# time_circuit_controller_1_2.net
KiCad netlist of a schematic drawn in EAGLE
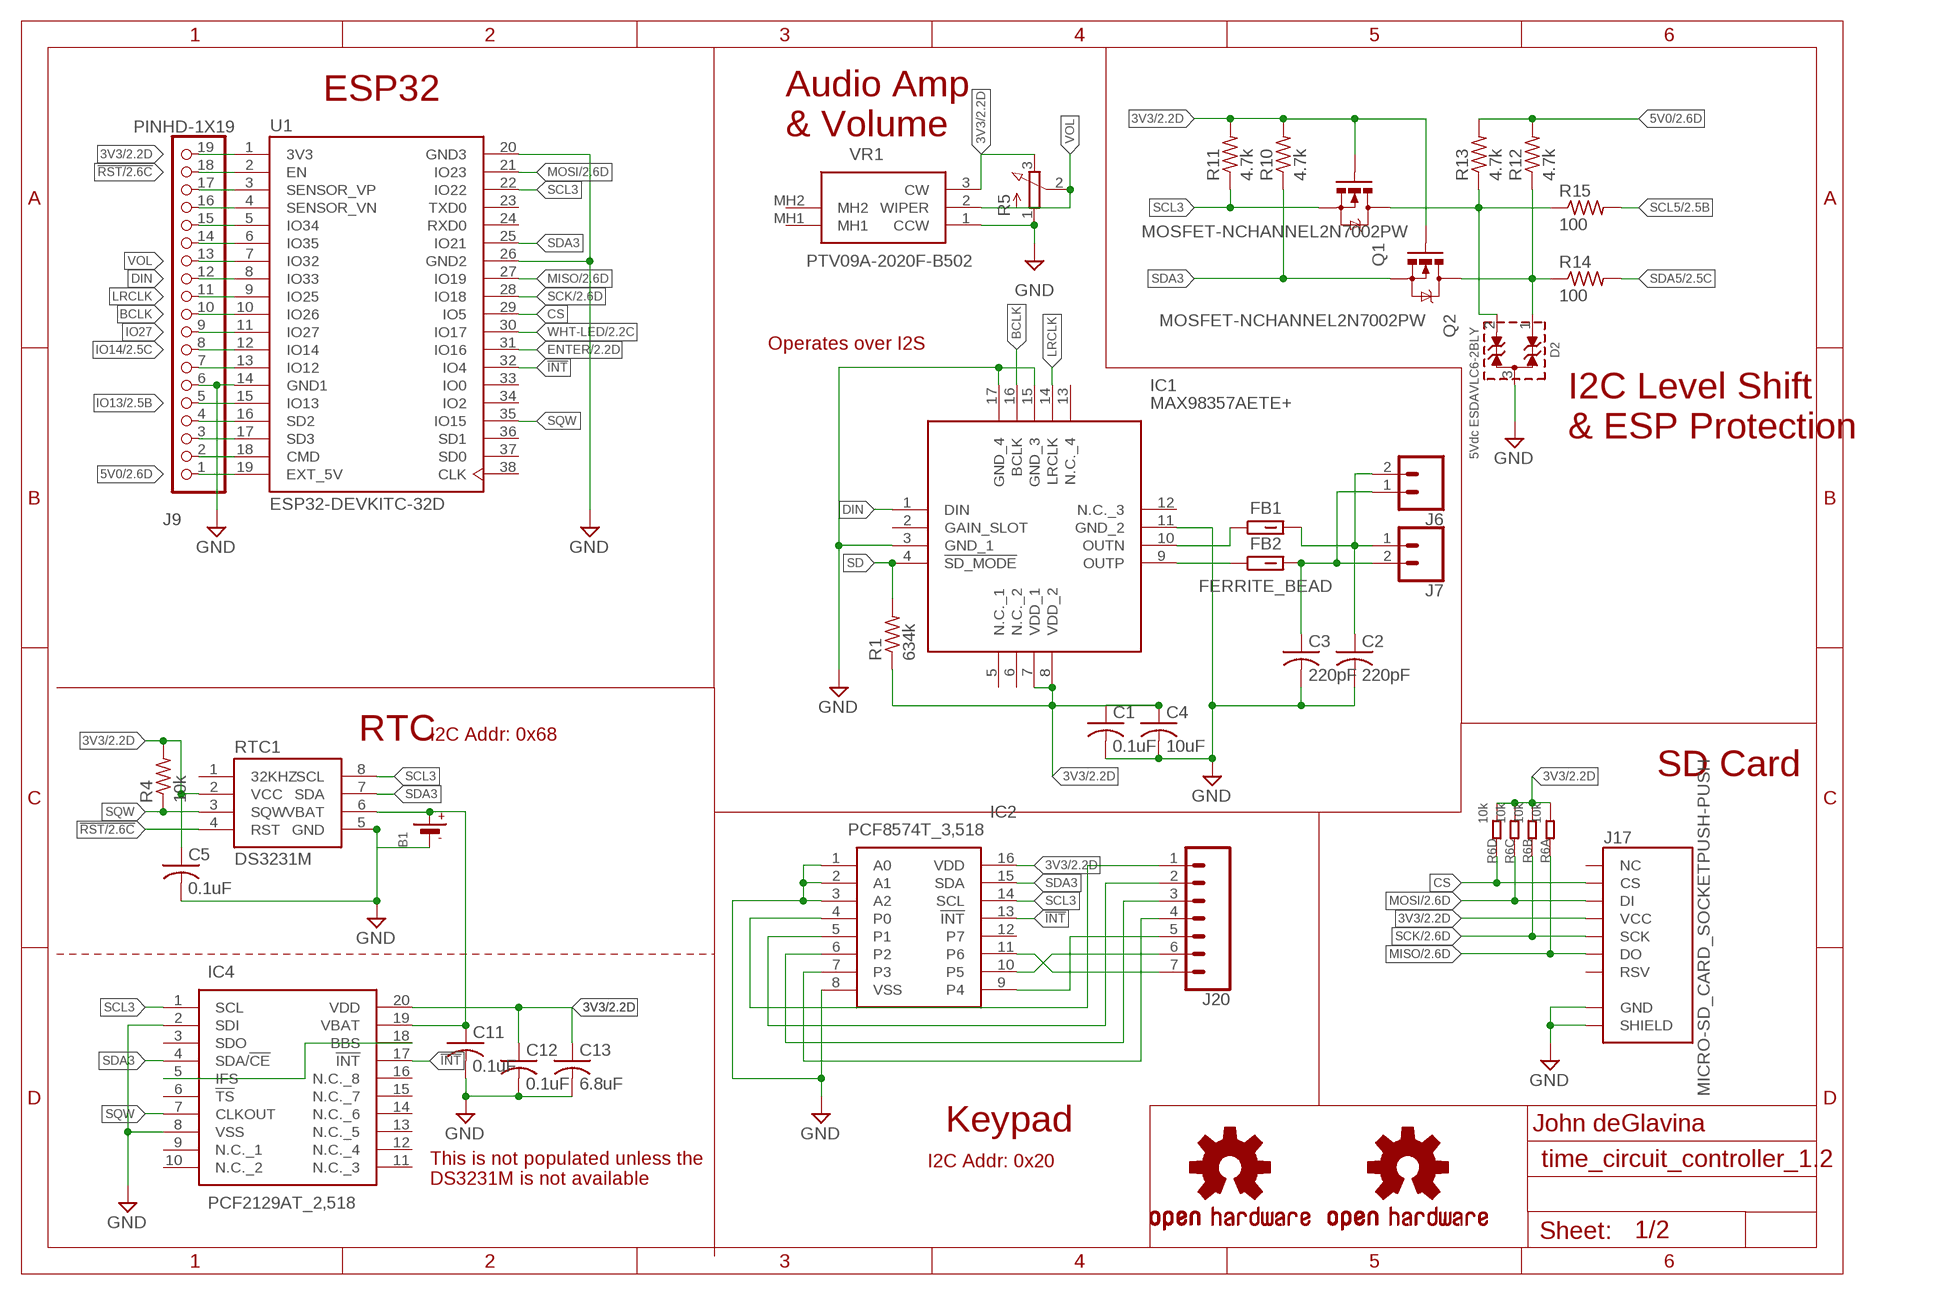
[diagram p0: schematic, sheet 1]
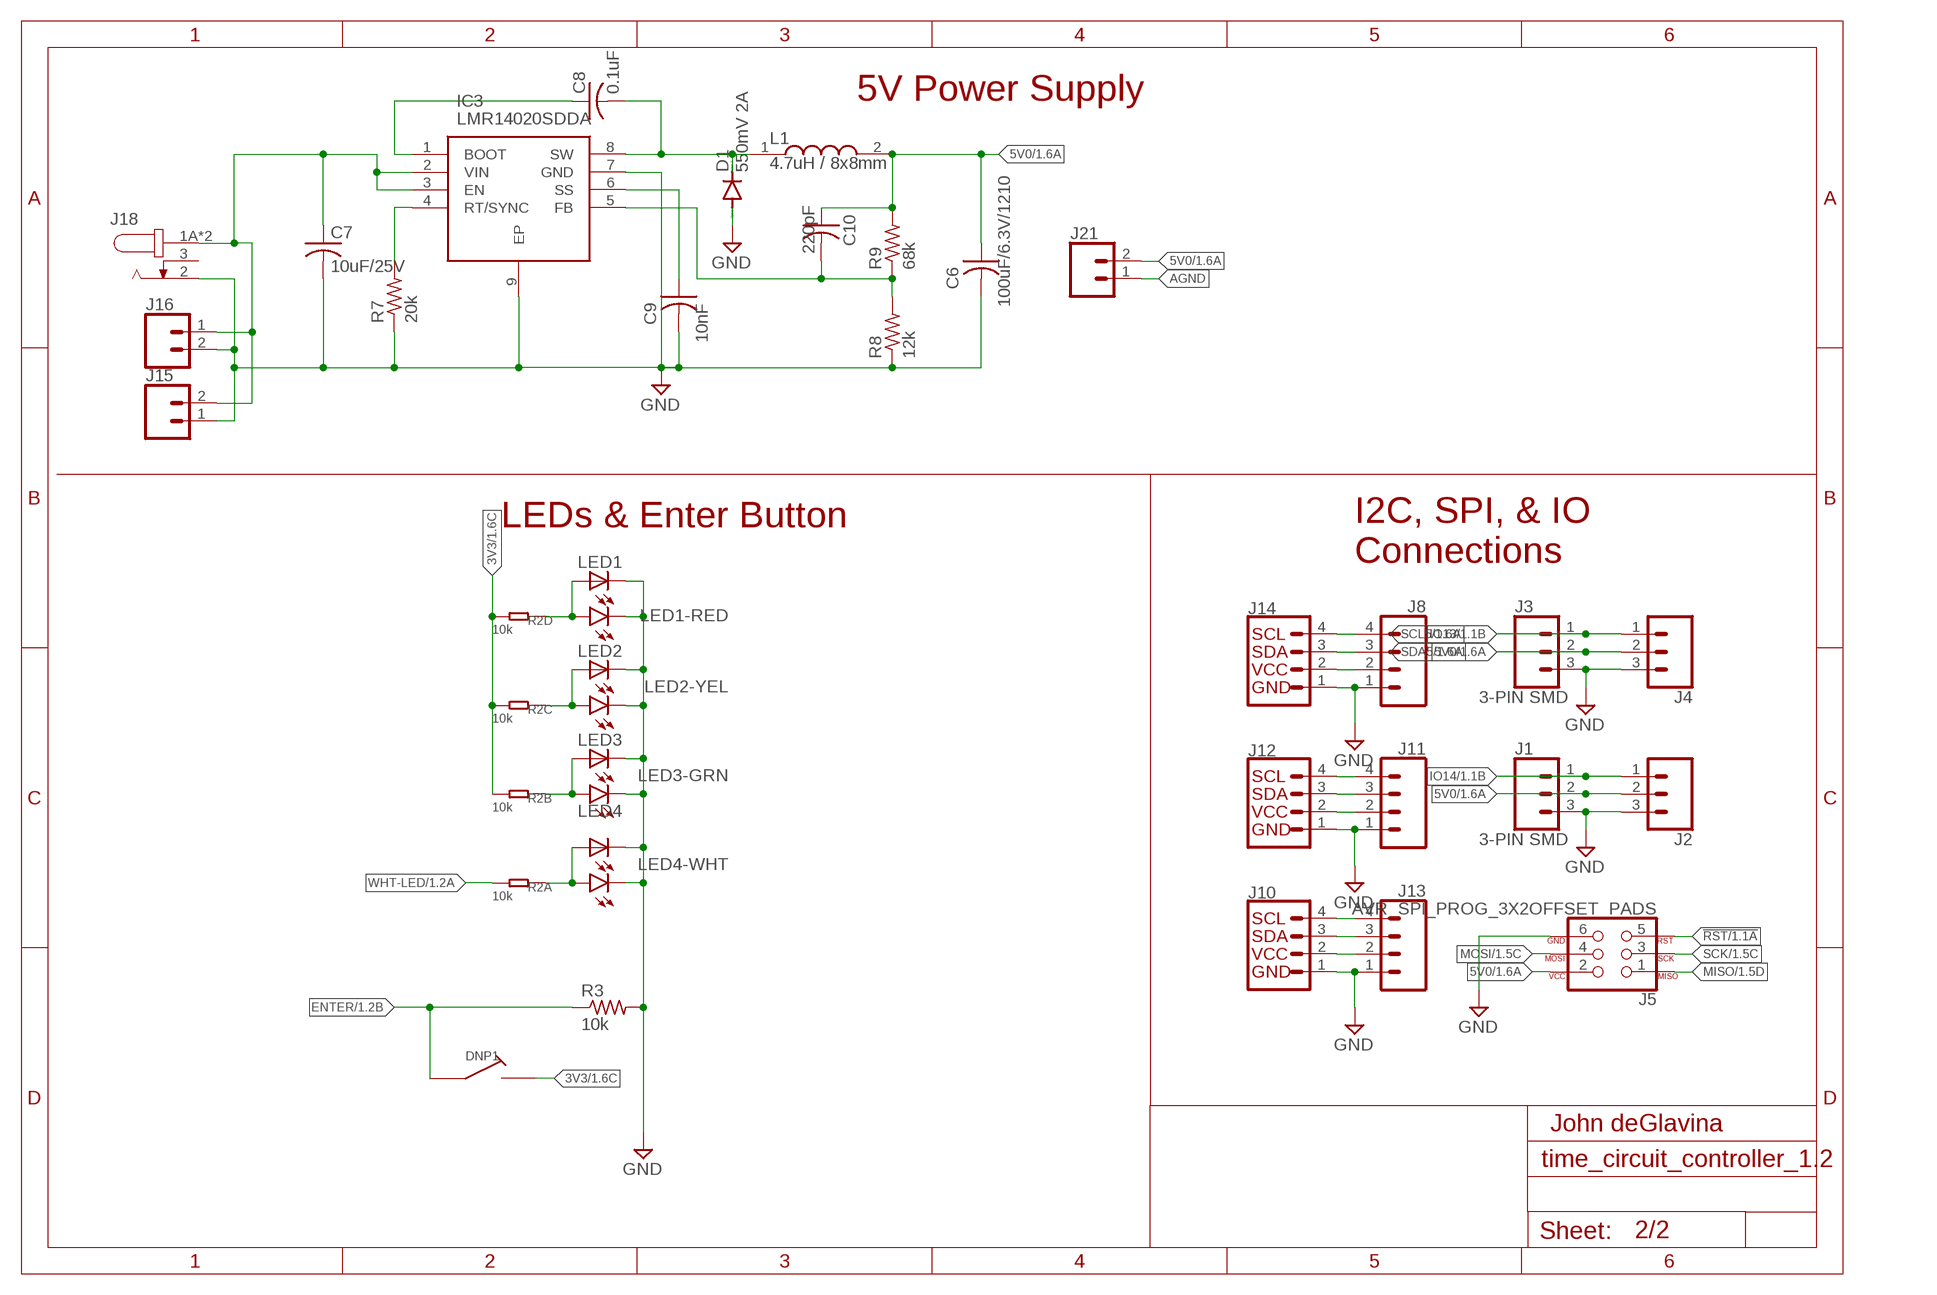
[diagram p1: schematic, sheet 2]

(export (version "E")
  (design (tool "Eeschema 10.0.6"))
  (components
    (comp (ref "C6")
      (value "100uF/6.3V/1210")
      (footprint "eagle-import:C1210")
      (libsource (lib "eagle-import") (part "C-USC1210"))
    )
    (comp (ref "C7")
      (value "10uF/25V")
      (footprint "eagle-import:C0805")
      (libsource (lib "eagle-import") (part "C-USC0805"))
    )
    (comp (ref "C8")
      (value "0.1uF")
      (footprint "eagle-import:C0603")
      (libsource (lib "eagle-import") (part "C-USC0603"))
    )
    (comp (ref "C9")
      (value "10nF")
      (footprint "eagle-import:C0603")
      (libsource (lib "eagle-import") (part "C-USC0603"))
    )
    (comp (ref "C10")
      (value "220pF")
      (footprint "eagle-import:C0603")
      (libsource (lib "eagle-import") (part "C-USC0603"))
    )
    (comp (ref "D1")
      (value "550mV 2A")
      (footprint "eagle-import:DO214AC")
      (libsource (lib "eagle-import") (part "DIODE-DO214AC"))
    )
    (comp (ref "DNP1")
      (value "SWITCH-PINHEAD")
      (footprint "eagle-import:PIN-1X2-3.5MM")
      (libsource (lib "eagle-import") (part "SWITCH-PINHEAD"))
    )
    (comp (ref "IC3")
      (value "LMR14020SDDA")
      (footprint "eagle-import:SOIC127P600X170-9N")
      (fields
        (field (name "MOUSER_PART_NUMBER") "595-LMR14020SDDA")
        (field (name "RS_PART_NUMBER") "1629813")
      )
      (libsource (lib "eagle-import") (part "LMR14020SDDA"))
    )
    (comp (ref "J1")
      (value "3-PIN SMD")
      (footprint "eagle-import:JST-3-SMD")
      (libsource (lib "eagle-import") (part "CONN_03JST-SMD"))
    )
    (comp (ref "J2")
      (value "CONN_03LOCK_LONGPADS")
      (footprint "eagle-import:1X03_LOCK_LONGPADS")
      (libsource (lib "eagle-import") (part "CONN_03LOCK_LONGPADS"))
    )
    (comp (ref "J3")
      (value "3-PIN SMD")
      (footprint "eagle-import:JST-3-SMD")
      (libsource (lib "eagle-import") (part "CONN_03JST-SMD"))
    )
    (comp (ref "J4")
      (value "CONN_03LOCK_LONGPADS")
      (footprint "eagle-import:1X03_LOCK_LONGPADS")
      (libsource (lib "eagle-import") (part "CONN_03LOCK_LONGPADS"))
    )
    (comp (ref "J5")
      (value "AVR_SPI_PROG_3X2OFFSET_PADS")
      (footprint "eagle-import:2X3_OFFSET")
      (libsource (lib "eagle-import") (part "AVR_SPI_PROG_3X2OFFSET_PADS"))
    )
    (comp (ref "J8")
      (value "CONN_04SMD_2.54")
      (footprint "eagle-import:1X04_5.5MM_STRAIGHT")
      (libsource (lib "eagle-import") (part "CONN_04SMD_2.54"))
    )
    (comp (ref "J10")
      (value "I2C_STANDARD")
      (footprint "eagle-import:1X04")
      (libsource (lib "eagle-import") (part "I2C_STANDARD"))
    )
    (comp (ref "J11")
      (value "CONN_04SMD_2.54")
      (footprint "eagle-import:1X04_5.5MM_STRAIGHT")
      (libsource (lib "eagle-import") (part "CONN_04SMD_2.54"))
    )
    (comp (ref "J12")
      (value "I2C_STANDARD")
      (footprint "eagle-import:1X04")
      (libsource (lib "eagle-import") (part "I2C_STANDARD"))
    )
    (comp (ref "J13")
      (value "CONN_04SMD_2.54")
      (footprint "eagle-import:1X04_5.5MM_STRAIGHT")
      (libsource (lib "eagle-import") (part "CONN_04SMD_2.54"))
    )
    (comp (ref "J14")
      (value "I2C_STANDARD")
      (footprint "eagle-import:1X04")
      (libsource (lib "eagle-import") (part "I2C_STANDARD"))
    )
    (comp (ref "J15")
      (value "CONN_023.5MM")
      (footprint "eagle-import:SCREWTERMINAL-3.5MM-2")
      (libsource (lib "eagle-import") (part "SparkFun-Connectors_8231346_CONN_023.5MM"))
    )
    (comp (ref "J16")
      (value "CONN_02-JST-2MM-SMT")
      (footprint "eagle-import:JST-2-SMD")
      (libsource (lib "eagle-import") (part "SparkFun-Connectors_8231346_CONN_02-JST-2MM-SMT"))
    )
    (comp (ref "J18")
      (value "9-12VAC")
      (footprint "eagle-import:CUI_PJ-002AH-SMT-TR")
      (fields (field (name "MF") "CUI") (field (name "MP") "PJ-002AH-SMT-TR"))
      (libsource (lib "eagle-import") (part "PJ-002AH-SMT-TR"))
    )
    (comp (ref "J21")
      (value "CONN_023.5MM")
      (footprint "eagle-import:SCREWTERMINAL-3.5MM-2")
      (libsource (lib "eagle-import") (part "SparkFun-Connectors_8231346_CONN_023.5MM"))
    )
    (comp (ref "L1")
      (value "4.7uH / 8x8mm")
      (footprint "eagle-import:INDPM8082X300N")
      (fields (field (name "MANUFACTURER_PART_NUMBER") "1273AS-H-3R3N=P3"))
      (libsource (lib "eagle-import") (part "1273AS-H-3R3N=P3"))
    )
    (comp (ref "LED1")
      (value "LEDCHIPLED_1206")
      (footprint "eagle-import:CHIPLED_1206")
      (libsource (lib "eagle-import") (part "LEDCHIPLED_1206"))
    )
    (comp (ref "LED1-RED")
      (value "LED5MM")
      (footprint "eagle-import:LED5MM")
      (libsource (lib "eagle-import") (part "led_259_LED5MM"))
    )
    (comp (ref "LED2")
      (value "LEDCHIPLED_1206")
      (footprint "eagle-import:CHIPLED_1206")
      (libsource (lib "eagle-import") (part "LEDCHIPLED_1206"))
    )
    (comp (ref "LED2-YEL")
      (value "LED5MM")
      (footprint "eagle-import:LED5MM")
      (libsource (lib "eagle-import") (part "led_259_LED5MM"))
    )
    (comp (ref "LED3")
      (value "LEDCHIPLED_1206")
      (footprint "eagle-import:CHIPLED_1206")
      (libsource (lib "eagle-import") (part "LEDCHIPLED_1206"))
    )
    (comp (ref "LED3-GRN")
      (value "LED5MM")
      (footprint "eagle-import:LED5MM")
      (libsource (lib "eagle-import") (part "led_259_LED5MM"))
    )
    (comp (ref "LED4")
      (value "LEDCHIPLED_1206")
      (footprint "eagle-import:CHIPLED_1206")
      (libsource (lib "eagle-import") (part "LEDCHIPLED_1206"))
    )
    (comp (ref "LED4-WHT")
      (value "LED5MM")
      (footprint "eagle-import:LED5MM")
      (libsource (lib "eagle-import") (part "led_259_LED5MM"))
    )
    (comp (ref "R2")
      (value "10k")
      (footprint "eagle-import:RA1206-8")
      (libsource (lib "eagle-import") (part "RES-ARRAY-1206"))
    )
    (comp (ref "R3")
      (value "10k")
      (footprint "eagle-import:R0603")
      (libsource (lib "eagle-import") (part "R-US_R0603"))
    )
    (comp (ref "R7")
      (value "20k")
      (footprint "eagle-import:R0603")
      (libsource (lib "eagle-import") (part "R-US_R0603"))
    )
    (comp (ref "R8")
      (value "12k")
      (footprint "eagle-import:R0603")
      (libsource (lib "eagle-import") (part "R-US_R0603"))
    )
    (comp (ref "R9")
      (value "68k")
      (footprint "eagle-import:R0603")
      (libsource (lib "eagle-import") (part "R-US_R0603"))
    )
    (comp (ref "B1")
      (value "BATTERYCR2032_BAT-HLD-001")
      (footprint "eagle-import:CR2032_SMT_BAT-HLD-001")
      (libsource (lib "eagle-import") (part "BATTERYCR2032_BAT-HLD-001"))
    )
    (comp (ref "C1")
      (value "0.1uF")
      (footprint "eagle-import:C0603")
      (libsource (lib "eagle-import") (part "C-USC0603"))
    )
    (comp (ref "C2")
      (value "220pF")
      (footprint "eagle-import:C0603")
      (libsource (lib "eagle-import") (part "C-USC0603"))
    )
    (comp (ref "C3")
      (value "220pF")
      (footprint "eagle-import:C0603")
      (libsource (lib "eagle-import") (part "C-USC0603"))
    )
    (comp (ref "C4")
      (value "10uF")
      (footprint "eagle-import:C0603")
      (libsource (lib "eagle-import") (part "C-USC0603"))
    )
    (comp (ref "C5")
      (value "0.1uF")
      (footprint "eagle-import:C0603")
      (libsource (lib "eagle-import") (part "C-USC0603"))
    )
    (comp (ref "C11")
      (value "0.1uF")
      (footprint "eagle-import:C0603")
      (libsource (lib "eagle-import") (part "C-USC0603"))
    )
    (comp (ref "C12")
      (value "0.1uF")
      (footprint "eagle-import:C0603")
      (libsource (lib "eagle-import") (part "C-USC0603"))
    )
    (comp (ref "C13")
      (value "6.8uF")
      (footprint "eagle-import:C0603")
      (libsource (lib "eagle-import") (part "C-USC0603"))
    )
    (comp (ref "D2")
      (value "5Vdc ESDAVLC6-2BLY")
      (footprint "eagle-import:WE-TVS_SOT23-3L")
      (libsource (lib "eagle-import") (part "WE-TVS_SOT23-3L_824022"))
    )
    (comp (ref "FB1")
      (value "FERRITE_BEAD")
      (footprint "eagle-import:BEADC1608X95N")
      (libsource (lib "eagle-import") (part "FBCHIP-0603(1608-METRIC)"))
    )
    (comp (ref "FB2")
      (value "FERRITE_BEAD")
      (footprint "eagle-import:BEADC1608X95N")
      (libsource (lib "eagle-import") (part "FBCHIP-0603(1608-METRIC)"))
    )
    (comp (ref "IC1")
      (value "MAX98357AETE+")
      (footprint "eagle-import:QFN50P300X300X80-17N")
      (fields (field (name "MOUSER_PART_NUMBER") "700-MAX98357AETE+"))
      (libsource (lib "eagle-import") (part "MAX98357AETE+"))
    )
    (comp (ref "IC2")
      (value "PCF8574T_3,518")
      (footprint "eagle-import:SOIC127P1032X265-16N")
      (fields
        (field (name "ARROW_PART_NUMBER") "PCF8574T/3,518")
        (field (name "MOUSER_PART_NUMBER") "771-PCF8574TD-T")
      )
      (libsource (lib "eagle-import") (part "PCF8574T_3,518"))
    )
    (comp (ref "IC4")
      (value "PCF2129AT_2,518")
      (footprint "eagle-import:SOIC127P1032X265-20N")
      (fields
        (field (name "ARROW_PART_NUMBER") "PCF2129AT/2,518")
        (field (name "MOUSER_PART_NUMBER") "771-PCF2129AT/2,518")
      )
      (libsource (lib "eagle-import") (part "PCF2129AT_2,518"))
    )
    (comp (ref "J6")
      (value "CONN_02-JST-2MM-SMT")
      (footprint "eagle-import:JST-2-SMD")
      (libsource (lib "eagle-import") (part "SparkFun-Connectors_8231346_CONN_02-JST-2MM-SMT"))
    )
    (comp (ref "J7")
      (value "CONN_02")
      (footprint "eagle-import:1X02")
      (libsource (lib "eagle-import") (part "CONN_02"))
    )
    (comp (ref "J9")
      (value "PINHD-1X19")
      (footprint "eagle-import:1X19")
      (libsource (lib "eagle-import") (part "PINHD-1X19"))
    )
    (comp (ref "J17")
      (value "MICRO-SD_CARD_SOCKETPUSH-PUSH")
      (footprint "eagle-import:MICRO-SD-SOCKET")
      (libsource (lib "eagle-import") (part "MICRO-SD_CARD_SOCKETPUSH-PUSH"))
    )
    (comp (ref "J20")
      (value "CONN_07LOCK")
      (footprint "eagle-import:1X07_LOCK")
      (libsource (lib "eagle-import") (part "CONN_07LOCK"))
    )
    (comp (ref "LOGO1")
      (value "OSHW-LOGOL")
      (footprint "eagle-import:OSHW-LOGO-L")
      (libsource (lib "eagle-import") (part "OSHW-LOGOL"))
    )
    (comp (ref "LOGO2")
      (value "OSHW-LOGOL")
      (footprint "eagle-import:OSHW-LOGO-L")
      (libsource (lib "eagle-import") (part "OSHW-LOGOL"))
    )
    (comp (ref "Q1")
      (value "MOSFET-NCHANNEL2N7002PW")
      (footprint "eagle-import:SOT323")
      (libsource (lib "eagle-import") (part "MOSFET-NCHANNEL2N7002PW"))
    )
    (comp (ref "Q2")
      (value "MOSFET-NCHANNEL2N7002PW")
      (footprint "eagle-import:SOT323")
      (libsource (lib "eagle-import") (part "MOSFET-NCHANNEL2N7002PW"))
    )
    (comp (ref "R1")
      (value "634k")
      (footprint "eagle-import:R0603")
      (libsource (lib "eagle-import") (part "R-US_R0603"))
    )
    (comp (ref "R4")
      (value "10k")
      (footprint "eagle-import:R0603")
      (libsource (lib "eagle-import") (part "R-US_R0603"))
    )
    (comp (ref "R5")
      (value "3RP/1610N")
      (footprint "eagle-import:3RP_1610N")
      (libsource (lib "eagle-import") (part "3RP/1610N"))
    )
    (comp (ref "R6")
      (value "10k")
      (footprint "eagle-import:RA1206-8")
      (libsource (lib "eagle-import") (part "RES-ARRAY-1206"))
    )
    (comp (ref "R10")
      (value "4.7k")
      (footprint "eagle-import:R0603")
      (libsource (lib "eagle-import") (part "R-US_R0603"))
    )
    (comp (ref "R11")
      (value "4.7k")
      (footprint "eagle-import:R0603")
      (libsource (lib "eagle-import") (part "R-US_R0603"))
    )
    (comp (ref "R12")
      (value "4.7k")
      (footprint "eagle-import:R0603")
      (libsource (lib "eagle-import") (part "R-US_R0603"))
    )
    (comp (ref "R13")
      (value "4.7k")
      (footprint "eagle-import:R0603")
      (libsource (lib "eagle-import") (part "R-US_R0603"))
    )
    (comp (ref "R14")
      (value "100")
      (footprint "eagle-import:R0603")
      (libsource (lib "eagle-import") (part "R-US_R0603"))
    )
    (comp (ref "R15")
      (value "100")
      (footprint "eagle-import:R0603")
      (libsource (lib "eagle-import") (part "R-US_R0603"))
    )
    (comp (ref "RTC1")
      (value "DS3231M")
      (footprint "eagle-import:SO08")
      (libsource (lib "eagle-import") (part "DS3231M"))
    )
    (comp (ref "U1")
      (value "ESP32-DEVKITC-32D")
      (footprint "eagle-import:MODULE_ESP32-DEVKITC-32D")
      (fields (field (name "MF") "Espressif Systems"))
      (libsource (lib "eagle-import") (part "ESP32-DEVKITC-32D"))
    )
    (comp (ref "VR1")
      (value "PTV09A-2020F-B502")
      (footprint "eagle-import:PTV09A2020FB502")
      (fields (field (name "MOUSER_PART_NUMBER") "652-PTV09A-2020FB502"))
      (libsource (lib "eagle-import") (part "PTV09A-2020F-B502"))
    )
  )
  (nets
    (net (code "1") (name "3V3") (class "Default")
      (node (ref "C1") (pin "1") (pinfunction "1_1") (pintype "passive"))
      (node (ref "C12") (pin "1") (pinfunction "1_1") (pintype "passive"))
      (node (ref "C13") (pin "1") (pinfunction "1_1") (pintype "passive"))
      (node (ref "C4") (pin "1") (pinfunction "1_1") (pintype "passive"))
      (node (ref "C5") (pin "1") (pinfunction "1_1") (pintype "passive"))
      (node (ref "DNP1") (pin "P$2") (pinfunction "2_P$2") (pintype "bidirectional"))
      (node (ref "IC1") (pin "7") (pinfunction "VDD_1_7") (pintype "bidirectional"))
      (node (ref "IC1") (pin "8") (pinfunction "VDD_2_8") (pintype "bidirectional"))
      (node (ref "IC2") (pin "16") (pinfunction "VDD_16") (pintype "bidirectional"))
      (node (ref "IC4") (pin "20") (pinfunction "VDD_20") (pintype "bidirectional"))
      (node (ref "J17") (pin "VCC") (pinfunction "VCC_VCC") (pintype "bidirectional"))
      (node (ref "J9") (pin "19") (pinfunction "19_19") (pintype "passive"))
      (node (ref "Q1") (pin "1") (pinfunction "G_1") (pintype "passive"))
      (node (ref "Q2") (pin "1") (pinfunction "G_1") (pintype "passive"))
      (node (ref "R1") (pin "1") (pinfunction "1_1") (pintype "passive"))
      (node (ref "R10") (pin "2") (pinfunction "2_2") (pintype "passive"))
      (node (ref "R11") (pin "2") (pinfunction "2_2") (pintype "passive"))
      (node (ref "R2") (pin "2") (pinfunction "1_2") (pintype "passive"))
      (node (ref "R2") (pin "3") (pinfunction "1_3") (pintype "passive"))
      (node (ref "R2") (pin "4") (pinfunction "1_4") (pintype "passive"))
      (node (ref "R4") (pin "2") (pinfunction "2_2") (pintype "passive"))
      (node (ref "R5") (pin "3") (pinfunction "E_3") (pintype "passive"))
      (node (ref "R6") (pin "1") (pinfunction "1_1") (pintype "passive"))
      (node (ref "R6") (pin "2") (pinfunction "1_2") (pintype "passive"))
      (node (ref "R6") (pin "3") (pinfunction "1_3") (pintype "passive"))
      (node (ref "R6") (pin "4") (pinfunction "1_4") (pintype "passive"))
      (node (ref "RTC1") (pin "2") (pinfunction "VCC_2") (pintype "power_in"))
      (node (ref "U1") (pin "1") (pinfunction "3V3_1") (pintype "power_in"))
      (node (ref "VR1") (pin "3") (pinfunction "CW_3") (pintype "bidirectional"))
    )
    (net (code "2") (name "5V0") (class "Default")
      (node (ref "C10") (pin "1") (pinfunction "1_1") (pintype "passive"))
      (node (ref "C6") (pin "1") (pinfunction "1_1") (pintype "passive"))
      (node (ref "J1") (pin "2") (pinfunction "2_2") (pintype "passive"))
      (node (ref "J10") (pin "2") (pinfunction "2_2") (pintype "power_in"))
      (node (ref "J11") (pin "2") (pinfunction "2_2") (pintype "passive"))
      (node (ref "J12") (pin "2") (pinfunction "2_2") (pintype "power_in"))
      (node (ref "J13") (pin "2") (pinfunction "2_2") (pintype "passive"))
      (node (ref "J14") (pin "2") (pinfunction "2_2") (pintype "power_in"))
      (node (ref "J2") (pin "2") (pinfunction "2_2") (pintype "passive"))
      (node (ref "J21") (pin "2") (pinfunction "2_2") (pintype "passive"))
      (node (ref "J3") (pin "2") (pinfunction "2_2") (pintype "passive"))
      (node (ref "J4") (pin "2") (pinfunction "2_2") (pintype "passive"))
      (node (ref "J5") (pin "2") (pinfunction "2_2") (pintype "passive"))
      (node (ref "J8") (pin "2") (pinfunction "2_2") (pintype "passive"))
      (node (ref "J9") (pin "1") (pinfunction "1_1") (pintype "passive"))
      (node (ref "L1") (pin "2") (pinfunction "2_2") (pintype "power_in"))
      (node (ref "R12") (pin "2") (pinfunction "2_2") (pintype "passive"))
      (node (ref "R13") (pin "2") (pinfunction "2_2") (pintype "passive"))
      (node (ref "R9") (pin "2") (pinfunction "2_2") (pintype "passive"))
      (node (ref "U1") (pin "19") (pinfunction "EXT_5V_19") (pintype "power_in"))
    )
    (net (code "3") (name "AGND") (class "Default")
      (node (ref "B1") (pin "-") (pinfunction "-_-") (pintype "passive"))
      (node (ref "C1") (pin "2") (pinfunction "2_2") (pintype "passive"))
      (node (ref "C11") (pin "2") (pinfunction "2_2") (pintype "passive"))
      (node (ref "C12") (pin "2") (pinfunction "2_2") (pintype "passive"))
      (node (ref "C13") (pin "2") (pinfunction "2_2") (pintype "passive"))
      (node (ref "C2") (pin "2") (pinfunction "2_2") (pintype "passive"))
      (node (ref "C3") (pin "2") (pinfunction "2_2") (pintype "passive"))
      (node (ref "C4") (pin "2") (pinfunction "2_2") (pintype "passive"))
      (node (ref "C5") (pin "2") (pinfunction "2_2") (pintype "passive"))
      (node (ref "C6") (pin "2") (pinfunction "2_2") (pintype "passive"))
      (node (ref "C7") (pin "2") (pinfunction "2_2") (pintype "passive"))
      (node (ref "C9") (pin "2") (pinfunction "2_2") (pintype "passive"))
      (node (ref "D1") (pin "A") (pinfunction "A_A") (pintype "passive"))
      (node (ref "D2") (pin "3") (pinfunction "GND_3") (pintype "power_in"))
      (node (ref "IC1") (pin "11") (pinfunction "GND_2_11") (pintype "bidirectional"))
      (node (ref "IC1") (pin "15") (pinfunction "GND_3_15") (pintype "bidirectional"))
      (node (ref "IC1") (pin "17") (pinfunction "GND_4_17") (pintype "bidirectional"))
      (node (ref "IC1") (pin "3") (pinfunction "GND_1_3") (pintype "bidirectional"))
      (node (ref "IC2") (pin "1") (pinfunction "A0_1") (pintype "bidirectional"))
      (node (ref "IC2") (pin "2") (pinfunction "A1_2") (pintype "bidirectional"))
      (node (ref "IC2") (pin "3") (pinfunction "A2_3") (pintype "bidirectional"))
      (node (ref "IC2") (pin "8") (pinfunction "VSS_8") (pintype "bidirectional"))
      (node (ref "IC3") (pin "7") (pinfunction "GND_7") (pintype "power_in"))
      (node (ref "IC3") (pin "9") (pinfunction "EP_9") (pintype "power_in"))
      (node (ref "IC4") (pin "2") (pinfunction "SDI_2") (pintype "bidirectional"))
      (node (ref "IC4") (pin "8") (pinfunction "VSS_8") (pintype "bidirectional"))
      (node (ref "J1") (pin "3") (pinfunction "1_3") (pintype "passive"))
      (node (ref "J10") (pin "1") (pinfunction "1_1") (pintype "power_in"))
      (node (ref "J11") (pin "1") (pinfunction "1_1") (pintype "passive"))
      (node (ref "J12") (pin "1") (pinfunction "1_1") (pintype "power_in"))
      (node (ref "J13") (pin "1") (pinfunction "1_1") (pintype "passive"))
      (node (ref "J14") (pin "1") (pinfunction "1_1") (pintype "power_in"))
      (node (ref "J15") (pin "1") (pinfunction "1_1") (pintype "passive"))
      (node (ref "J16") (pin "2") (pinfunction "1_2") (pintype "passive"))
      (node (ref "J17") (pin "CD1") (pinfunction "SHIELD_CD1") (pintype "bidirectional"))
      (node (ref "J17") (pin "GND") (pinfunction "GND_GND") (pintype "bidirectional"))
      (node (ref "J18") (pin "2") (pinfunction "2_2") (pintype "passive"))
      (node (ref "J2") (pin "3") (pinfunction "3_3") (pintype "passive"))
      (node (ref "J21") (pin "1") (pinfunction "1_1") (pintype "passive"))
      (node (ref "J3") (pin "3") (pinfunction "1_3") (pintype "passive"))
      (node (ref "J4") (pin "3") (pinfunction "3_3") (pintype "passive"))
      (node (ref "J5") (pin "6") (pinfunction "6_6") (pintype "passive"))
      (node (ref "J8") (pin "1") (pinfunction "1_1") (pintype "passive"))
      (node (ref "J9") (pin "6") (pinfunction "6_6") (pintype "passive"))
      (node (ref "LED1") (pin "C") (pinfunction "C_C") (pintype "passive"))
      (node (ref "LED1-RED") (pin "K") (pinfunction "C_K") (pintype "passive"))
      (node (ref "LED2") (pin "C") (pinfunction "C_C") (pintype "passive"))
      (node (ref "LED2-YEL") (pin "K") (pinfunction "C_K") (pintype "passive"))
      (node (ref "LED3") (pin "C") (pinfunction "C_C") (pintype "passive"))
      (node (ref "LED3-GRN") (pin "K") (pinfunction "C_K") (pintype "passive"))
      (node (ref "LED4") (pin "C") (pinfunction "C_C") (pintype "passive"))
      (node (ref "LED4-WHT") (pin "K") (pinfunction "C_K") (pintype "passive"))
      (node (ref "R3") (pin "2") (pinfunction "2_2") (pintype "passive"))
      (node (ref "R5") (pin "1") (pinfunction "A_1") (pintype "passive"))
      (node (ref "R7") (pin "1") (pinfunction "1_1") (pintype "passive"))
      (node (ref "R8") (pin "1") (pinfunction "1_1") (pintype "passive"))
      (node (ref "RTC1") (pin "5") (pinfunction "GND_5") (pintype "power_in"))
      (node (ref "U1") (pin "14") (pinfunction "GND1_14") (pintype "power_in"))
      (node (ref "U1") (pin "20") (pinfunction "GND3_20") (pintype "power_in"))
      (node (ref "U1") (pin "26") (pinfunction "GND2_26") (pintype "power_in"))
      (node (ref "VR1") (pin "1") (pinfunction "CCW_1") (pintype "bidirectional"))
    )
    (net (code "4") (name "BCLK") (class "Default")
      (node (ref "IC1") (pin "16") (pinfunction "BCLK_16") (pintype "bidirectional"))
      (node (ref "J9") (pin "10") (pinfunction "10_10") (pintype "passive"))
      (node (ref "U1") (pin "10") (pinfunction "IO26_10") (pintype "bidirectional"))
    )
    (net (code "5") (name "CS") (class "Default")
      (node (ref "J17") (pin "CS") (pinfunction "CS_CS") (pintype "bidirectional"))
      (node (ref "R6") (pin "5") (pinfunction "2_5") (pintype "passive"))
      (node (ref "U1") (pin "29") (pinfunction "IO5_29") (pintype "bidirectional"))
    )
    (net (code "6") (name "DIN") (class "Default")
      (node (ref "IC1") (pin "1") (pinfunction "DIN_1") (pintype "bidirectional"))
      (node (ref "J9") (pin "12") (pinfunction "12_12") (pintype "passive"))
      (node (ref "U1") (pin "8") (pinfunction "IO33_8") (pintype "bidirectional"))
    )
    (net (code "7") (name "ENTER") (class "Default")
      (node (ref "DNP1") (pin "P$1") (pinfunction "1_P$1") (pintype "bidirectional"))
      (node (ref "R3") (pin "1") (pinfunction "1_1") (pintype "passive"))
      (node (ref "U1") (pin "31") (pinfunction "IO16_31") (pintype "bidirectional"))
    )
    (net (code "8") (name "IO13") (class "Default")
      (node (ref "J3") (pin "1") (pinfunction "3_1") (pintype "passive"))
      (node (ref "J4") (pin "1") (pinfunction "1_1") (pintype "passive"))
      (node (ref "J9") (pin "5") (pinfunction "5_5") (pintype "passive"))
      (node (ref "U1") (pin "15") (pinfunction "IO13_15") (pintype "bidirectional"))
    )
    (net (code "9") (name "IO14") (class "Default")
      (node (ref "J1") (pin "1") (pinfunction "3_1") (pintype "passive"))
      (node (ref "J2") (pin "1") (pinfunction "1_1") (pintype "passive"))
      (node (ref "J9") (pin "8") (pinfunction "8_8") (pintype "passive"))
      (node (ref "U1") (pin "12") (pinfunction "IO14_12") (pintype "bidirectional"))
    )
    (net (code "10") (name "IO27") (class "Default")
      (node (ref "J9") (pin "9") (pinfunction "9_9") (pintype "passive"))
      (node (ref "U1") (pin "11") (pinfunction "IO27_11") (pintype "bidirectional"))
    )
    (net (code "11") (name "LRCLK") (class "Default")
      (node (ref "IC1") (pin "14") (pinfunction "LRCLK_14") (pintype "bidirectional"))
      (node (ref "J9") (pin "11") (pinfunction "11_11") (pintype "passive"))
      (node (ref "U1") (pin "9") (pinfunction "IO25_9") (pintype "bidirectional"))
    )
    (net (code "12") (name "MISO") (class "Default")
      (node (ref "J17") (pin "DO") (pinfunction "DO_DO") (pintype "bidirectional"))
      (node (ref "J5") (pin "1") (pinfunction "1_1") (pintype "passive"))
      (node (ref "R6") (pin "8") (pinfunction "2_8") (pintype "passive"))
      (node (ref "U1") (pin "27") (pinfunction "IO19_27") (pintype "bidirectional"))
    )
    (net (code "13") (name "MOSI") (class "Default")
      (node (ref "J17") (pin "DI") (pinfunction "DI_DI") (pintype "bidirectional"))
      (node (ref "J5") (pin "4") (pinfunction "4_4") (pintype "passive"))
      (node (ref "R6") (pin "6") (pinfunction "2_6") (pintype "passive"))
      (node (ref "U1") (pin "21") (pinfunction "IO23_21") (pintype "bidirectional"))
    )
    (net (code "14") (name "Net-(D2-I{slash}O1)") (class "Default")
      (node (ref "D2") (pin "1") (pinfunction "I/O1_1") (pintype "bidirectional"))
      (node (ref "Q2") (pin "3") (pinfunction "D_3") (pintype "passive"))
      (node (ref "R12") (pin "1") (pinfunction "1_1") (pintype "passive"))
      (node (ref "R14") (pin "1") (pinfunction "1_1") (pintype "passive"))
    )
    (net (code "15") (name "Net-(D2-I{slash}O2)") (class "Default")
      (node (ref "D2") (pin "2") (pinfunction "I/O2_2") (pintype "bidirectional"))
      (node (ref "Q1") (pin "3") (pinfunction "D_3") (pintype "passive"))
      (node (ref "R13") (pin "1") (pinfunction "1_1") (pintype "passive"))
      (node (ref "R15") (pin "1") (pinfunction "1_1") (pintype "passive"))
    )
    (net (code "16") (name "Net-(IC1-OUTN)") (class "Default")
      (node (ref "FB1") (pin "1") (pinfunction "1_1") (pintype "passive"))
      (node (ref "IC1") (pin "10") (pinfunction "OUTN_10") (pintype "bidirectional"))
    )
    (net (code "17") (name "Net-(IC1-OUTP)") (class "Default")
      (node (ref "FB2") (pin "1") (pinfunction "1_1") (pintype "passive"))
      (node (ref "IC1") (pin "9") (pinfunction "OUTP_9") (pintype "bidirectional"))
    )
    (net (code "18") (name "Net-(IC2-P0)") (class "Default")
      (node (ref "IC2") (pin "4") (pinfunction "P0_4") (pintype "bidirectional"))
      (node (ref "J20") (pin "1") (pinfunction "1_1") (pintype "passive"))
    )
    (net (code "19") (name "Net-(IC2-P1)") (class "Default")
      (node (ref "IC2") (pin "5") (pinfunction "P1_5") (pintype "bidirectional"))
      (node (ref "J20") (pin "2") (pinfunction "2_2") (pintype "passive"))
    )
    (net (code "20") (name "Net-(IC2-P2)") (class "Default")
      (node (ref "IC2") (pin "6") (pinfunction "P2_6") (pintype "bidirectional"))
      (node (ref "J20") (pin "3") (pinfunction "3_3") (pintype "passive"))
    )
    (net (code "21") (name "Net-(IC2-P3)") (class "Default")
      (node (ref "IC2") (pin "7") (pinfunction "P3_7") (pintype "bidirectional"))
      (node (ref "J20") (pin "4") (pinfunction "4_4") (pintype "passive"))
    )
    (net (code "22") (name "Net-(IC2-P4)") (class "Default")
      (node (ref "IC2") (pin "9") (pinfunction "P4_9") (pintype "bidirectional"))
      (node (ref "J20") (pin "5") (pinfunction "5_5") (pintype "passive"))
    )
    (net (code "23") (name "Net-(IC2-P5)") (class "Default")
      (node (ref "IC2") (pin "10") (pinfunction "P5_10") (pintype "bidirectional"))
      (node (ref "J20") (pin "6") (pinfunction "6_6") (pintype "passive"))
    )
    (net (code "24") (name "Net-(IC2-P6)") (class "Default")
      (node (ref "IC2") (pin "11") (pinfunction "P6_11") (pintype "bidirectional"))
      (node (ref "J20") (pin "7") (pinfunction "7_7") (pintype "passive"))
    )
    (net (code "25") (name "Net-(IC3-BOOT)") (class "Default")
      (node (ref "C8") (pin "1") (pinfunction "1_1") (pintype "passive"))
      (node (ref "IC3") (pin "1") (pinfunction "BOOT_1") (pintype "bidirectional"))
    )
    (net (code "26") (name "Net-(IC3-EN)") (class "Default")
      (node (ref "C7") (pin "1") (pinfunction "1_1") (pintype "passive"))
      (node (ref "IC3") (pin "2") (pinfunction "VIN_2") (pintype "input"))
      (node (ref "IC3") (pin "3") (pinfunction "EN_3") (pintype "bidirectional"))
      (node (ref "J15") (pin "2") (pinfunction "2_2") (pintype "passive"))
      (node (ref "J16") (pin "1") (pinfunction "2_1") (pintype "passive"))
      (node (ref "J18") (pin "1A") (pinfunction "1_1A") (pintype "passive"))
      (node (ref "J18") (pin "1B") (pinfunction "1_1B") (pintype "passive"))
    )
    (net (code "27") (name "Net-(IC3-FB)") (class "Default")
      (node (ref "C10") (pin "2") (pinfunction "2_2") (pintype "passive"))
      (node (ref "IC3") (pin "5") (pinfunction "FB_5") (pintype "bidirectional"))
      (node (ref "R8") (pin "2") (pinfunction "2_2") (pintype "passive"))
      (node (ref "R9") (pin "1") (pinfunction "1_1") (pintype "passive"))
    )
    (net (code "28") (name "Net-(IC3-RT{slash}SYNC)") (class "Default")
      (node (ref "IC3") (pin "4") (pinfunction "RT/SYNC_4") (pintype "bidirectional"))
      (node (ref "R7") (pin "2") (pinfunction "2_2") (pintype "passive"))
    )
    (net (code "29") (name "Net-(IC3-SS)") (class "Default")
      (node (ref "C9") (pin "1") (pinfunction "1_1") (pintype "passive"))
      (node (ref "IC3") (pin "6") (pinfunction "SS_6") (pintype "bidirectional"))
    )
    (net (code "30") (name "Net-(IC3-SW)") (class "Default")
      (node (ref "C8") (pin "2") (pinfunction "2_2") (pintype "passive"))
      (node (ref "D1") (pin "C") (pinfunction "C_C") (pintype "passive"))
      (node (ref "IC3") (pin "8") (pinfunction "SW_8") (pintype "bidirectional"))
      (node (ref "L1") (pin "1") (pinfunction "1_1") (pintype "power_in"))
    )
    (net (code "31") (name "Net-(IC4-BBS)") (class "Default")
      (node (ref "IC4") (pin "18") (pinfunction "BBS_18") (pintype "bidirectional"))
      (node (ref "IC4") (pin "5") (pinfunction "IFS_5") (pintype "bidirectional"))
    )
    (net (code "32") (name "Net-(IC4-VBAT)") (class "Default")
      (node (ref "B1") (pin "+$1") (pinfunction "+_+$1") (pintype "passive"))
      (node (ref "B1") (pin "+$2") (pinfunction "+_+$2") (pintype "passive"))
      (node (ref "C11") (pin "1") (pinfunction "1_1") (pintype "passive"))
      (node (ref "IC4") (pin "19") (pinfunction "VBAT_19") (pintype "bidirectional"))
      (node (ref "RTC1") (pin "6") (pinfunction "VBAT_6") (pintype "power_in"))
    )
    (net (code "33") (name "Net-(J6-1)") (class "Default")
      (node (ref "C2") (pin "1") (pinfunction "1_1") (pintype "passive"))
      (node (ref "FB1") (pin "2") (pinfunction "2_2") (pintype "passive"))
      (node (ref "J6") (pin "2") (pinfunction "1_2") (pintype "passive"))
      (node (ref "J7") (pin "1") (pinfunction "1_1") (pintype "passive"))
    )
    (net (code "34") (name "Net-(J6-2)") (class "Default")
      (node (ref "C3") (pin "1") (pinfunction "1_1") (pintype "passive"))
      (node (ref "FB2") (pin "2") (pinfunction "2_2") (pintype "passive"))
      (node (ref "J6") (pin "1") (pinfunction "2_1") (pintype "passive"))
      (node (ref "J7") (pin "2") (pinfunction "2_2") (pintype "passive"))
    )
    (net (code "35") (name "Net-(R2A-2)") (class "Default")
      (node (ref "LED4") (pin "A") (pinfunction "A_A") (pintype "passive"))
      (node (ref "LED4-WHT") (pin "A") (pinfunction "A_A") (pintype "passive"))
      (node (ref "R2") (pin "8") (pinfunction "2_8") (pintype "passive"))
    )
    (net (code "36") (name "Net-(R2B-2)") (class "Default")
      (node (ref "LED3") (pin "A") (pinfunction "A_A") (pintype "passive"))
      (node (ref "LED3-GRN") (pin "A") (pinfunction "A_A") (pintype "passive"))
      (node (ref "R2") (pin "7") (pinfunction "2_7") (pintype "passive"))
    )
    (net (code "37") (name "Net-(R2C-2)") (class "Default")
      (node (ref "LED2") (pin "A") (pinfunction "A_A") (pintype "passive"))
      (node (ref "LED2-YEL") (pin "A") (pinfunction "A_A") (pintype "passive"))
      (node (ref "R2") (pin "6") (pinfunction "2_6") (pintype "passive"))
    )
    (net (code "38") (name "Net-(R2D-2)") (class "Default")
      (node (ref "LED1") (pin "A") (pinfunction "A_A") (pintype "passive"))
      (node (ref "LED1-RED") (pin "A") (pinfunction "A_A") (pintype "passive"))
      (node (ref "R2") (pin "5") (pinfunction "2_5") (pintype "passive"))
    )
    (net (code "39") (name "Net-(U1-CMD)") (class "Default")
      (node (ref "J9") (pin "2") (pinfunction "2_2") (pintype "passive"))
      (node (ref "U1") (pin "18") (pinfunction "CMD_18") (pintype "bidirectional"))
    )
    (net (code "40") (name "Net-(U1-IO12)") (class "Default")
      (node (ref "J9") (pin "7") (pinfunction "7_7") (pintype "passive"))
      (node (ref "U1") (pin "13") (pinfunction "IO12_13") (pintype "bidirectional"))
    )
    (net (code "41") (name "Net-(U1-IO34)") (class "Default")
      (node (ref "J9") (pin "15") (pinfunction "15_15") (pintype "passive"))
      (node (ref "U1") (pin "5") (pinfunction "IO34_5") (pintype "bidirectional"))
    )
    (net (code "42") (name "Net-(U1-IO35)") (class "Default")
      (node (ref "J9") (pin "14") (pinfunction "14_14") (pintype "passive"))
      (node (ref "U1") (pin "6") (pinfunction "IO35_6") (pintype "bidirectional"))
    )
    (net (code "43") (name "Net-(U1-SD2)") (class "Default")
      (node (ref "J9") (pin "4") (pinfunction "4_4") (pintype "passive"))
      (node (ref "U1") (pin "16") (pinfunction "SD2_16") (pintype "bidirectional"))
    )
    (net (code "44") (name "Net-(U1-SD3)") (class "Default")
      (node (ref "J9") (pin "3") (pinfunction "3_3") (pintype "passive"))
      (node (ref "U1") (pin "17") (pinfunction "SD3_17") (pintype "bidirectional"))
    )
    (net (code "45") (name "Net-(U1-SENSOR_VN)") (class "Default")
      (node (ref "J9") (pin "16") (pinfunction "16_16") (pintype "passive"))
      (node (ref "U1") (pin "4") (pinfunction "SENSOR_VN_4") (pintype "input"))
    )
    (net (code "46") (name "Net-(U1-SENSOR_VP)") (class "Default")
      (node (ref "J9") (pin "17") (pinfunction "17_17") (pintype "passive"))
      (node (ref "U1") (pin "3") (pinfunction "SENSOR_VP_3") (pintype "input"))
    )
    (net (code "47") (name "SCK") (class "Default")
      (node (ref "J17") (pin "SCLK") (pinfunction "SCK_SCLK") (pintype "bidirectional"))
      (node (ref "J5") (pin "3") (pinfunction "3_3") (pintype "passive"))
      (node (ref "R6") (pin "7") (pinfunction "2_7") (pintype "passive"))
      (node (ref "U1") (pin "28") (pinfunction "IO18_28") (pintype "bidirectional"))
    )
    (net (code "48") (name "SCL3") (class "Default")
      (node (ref "IC2") (pin "14") (pinfunction "SCL_14") (pintype "bidirectional"))
      (node (ref "IC4") (pin "1") (pinfunction "SCL_1") (pintype "bidirectional"))
      (node (ref "Q1") (pin "2") (pinfunction "S_2") (pintype "passive"))
      (node (ref "R11") (pin "1") (pinfunction "1_1") (pintype "passive"))
      (node (ref "RTC1") (pin "8") (pinfunction "SCL_8") (pintype "bidirectional"))
      (node (ref "U1") (pin "22") (pinfunction "IO22_22") (pintype "bidirectional"))
    )
    (net (code "49") (name "SCL5") (class "Default")
      (node (ref "J10") (pin "4") (pinfunction "4_4") (pintype "passive"))
      (node (ref "J11") (pin "4") (pinfunction "4_4") (pintype "passive"))
      (node (ref "J12") (pin "4") (pinfunction "4_4") (pintype "passive"))
      (node (ref "J13") (pin "4") (pinfunction "4_4") (pintype "passive"))
      (node (ref "J14") (pin "4") (pinfunction "4_4") (pintype "passive"))
      (node (ref "J8") (pin "4") (pinfunction "4_4") (pintype "passive"))
      (node (ref "R15") (pin "2") (pinfunction "2_2") (pintype "passive"))
    )
    (net (code "50") (name "SD") (class "Default")
      (node (ref "IC1") (pin "4") (pinfunction "~{SD_MODE}_4") (pintype "bidirectional"))
      (node (ref "R1") (pin "2") (pinfunction "2_2") (pintype "passive"))
    )
    (net (code "51") (name "SDA3") (class "Default")
      (node (ref "IC2") (pin "15") (pinfunction "SDA_15") (pintype "bidirectional"))
      (node (ref "IC4") (pin "4") (pinfunction "SDA/~{CE}_4") (pintype "bidirectional"))
      (node (ref "Q2") (pin "2") (pinfunction "S_2") (pintype "passive"))
      (node (ref "R10") (pin "1") (pinfunction "1_1") (pintype "passive"))
      (node (ref "RTC1") (pin "7") (pinfunction "SDA_7") (pintype "bidirectional"))
      (node (ref "U1") (pin "25") (pinfunction "IO21_25") (pintype "bidirectional"))
    )
    (net (code "52") (name "SDA5") (class "Default")
      (node (ref "J10") (pin "3") (pinfunction "3_3") (pintype "passive"))
      (node (ref "J11") (pin "3") (pinfunction "3_3") (pintype "passive"))
      (node (ref "J12") (pin "3") (pinfunction "3_3") (pintype "passive"))
      (node (ref "J13") (pin "3") (pinfunction "3_3") (pintype "passive"))
      (node (ref "J14") (pin "3") (pinfunction "3_3") (pintype "passive"))
      (node (ref "J8") (pin "3") (pinfunction "3_3") (pintype "passive"))
      (node (ref "R14") (pin "2") (pinfunction "2_2") (pintype "passive"))
    )
    (net (code "53") (name "SQW") (class "Default")
      (node (ref "IC4") (pin "7") (pinfunction "CLKOUT_7") (pintype "bidirectional"))
      (node (ref "R4") (pin "1") (pinfunction "1_1") (pintype "passive"))
      (node (ref "RTC1") (pin "3") (pinfunction "SQW_3") (pintype "output"))
      (node (ref "U1") (pin "35") (pinfunction "IO15_35") (pintype "bidirectional"))
    )
    (net (code "54") (name "VOL") (class "Default")
      (node (ref "J9") (pin "13") (pinfunction "13_13") (pintype "passive"))
      (node (ref "R5") (pin "2") (pinfunction "S_2") (pintype "passive"))
      (node (ref "U1") (pin "7") (pinfunction "IO32_7") (pintype "bidirectional"))
      (node (ref "VR1") (pin "2") (pinfunction "WIPER_2") (pintype "bidirectional"))
    )
    (net (code "55") (name "WHT-LED") (class "Default")
      (node (ref "R2") (pin "1") (pinfunction "1_1") (pintype "passive"))
      (node (ref "U1") (pin "30") (pinfunction "IO17_30") (pintype "bidirectional"))
    )
    (net (code "56") (name "unconnected-(IC1-GAIN_SLOT-Pad2)") (class "Default")
      (node (ref "IC1") (pin "2") (pinfunction "GAIN_SLOT_2") (pintype "bidirectional"))
    )
    (net (code "57") (name "unconnected-(IC1-N.C._1-Pad5)") (class "Default")
      (node (ref "IC1") (pin "5") (pinfunction "N.C._1_5") (pintype "bidirectional"))
    )
    (net (code "58") (name "unconnected-(IC1-N.C._2-Pad6)") (class "Default")
      (node (ref "IC1") (pin "6") (pinfunction "N.C._2_6") (pintype "bidirectional"))
    )
    (net (code "59") (name "unconnected-(IC1-N.C._3-Pad12)") (class "Default")
      (node (ref "IC1") (pin "12") (pinfunction "N.C._3_12") (pintype "bidirectional"))
    )
    (net (code "60") (name "unconnected-(IC1-N.C._4-Pad13)") (class "Default")
      (node (ref "IC1") (pin "13") (pinfunction "N.C._4_13") (pintype "bidirectional"))
    )
    (net (code "61") (name "unconnected-(IC2-P7-Pad12)") (class "Default")
      (node (ref "IC2") (pin "12") (pinfunction "P7_12") (pintype "bidirectional"))
    )
    (net (code "62") (name "unconnected-(IC4-N.C._1-Pad9)") (class "Default")
      (node (ref "IC4") (pin "9") (pinfunction "N.C._1_9") (pintype "bidirectional"))
    )
    (net (code "63") (name "unconnected-(IC4-N.C._2-Pad10)") (class "Default")
      (node (ref "IC4") (pin "10") (pinfunction "N.C._2_10") (pintype "bidirectional"))
    )
    (net (code "64") (name "unconnected-(IC4-N.C._3-Pad11)") (class "Default")
      (node (ref "IC4") (pin "11") (pinfunction "N.C._3_11") (pintype "bidirectional"))
    )
    (net (code "65") (name "unconnected-(IC4-N.C._4-Pad12)") (class "Default")
      (node (ref "IC4") (pin "12") (pinfunction "N.C._4_12") (pintype "bidirectional"))
    )
    (net (code "66") (name "unconnected-(IC4-N.C._5-Pad13)") (class "Default")
      (node (ref "IC4") (pin "13") (pinfunction "N.C._5_13") (pintype "bidirectional"))
    )
    (net (code "67") (name "unconnected-(IC4-N.C._6-Pad14)") (class "Default")
      (node (ref "IC4") (pin "14") (pinfunction "N.C._6_14") (pintype "bidirectional"))
    )
    (net (code "68") (name "unconnected-(IC4-N.C._7-Pad15)") (class "Default")
      (node (ref "IC4") (pin "15") (pinfunction "N.C._7_15") (pintype "bidirectional"))
    )
    (net (code "69") (name "unconnected-(IC4-N.C._8-Pad16)") (class "Default")
      (node (ref "IC4") (pin "16") (pinfunction "N.C._8_16") (pintype "bidirectional"))
    )
    (net (code "70") (name "unconnected-(IC4-SDO-Pad3)") (class "Default")
      (node (ref "IC4") (pin "3") (pinfunction "SDO_3") (pintype "bidirectional"))
    )
    (net (code "71") (name "unconnected-(IC4-~{TS}-Pad6)") (class "Default")
      (node (ref "IC4") (pin "6") (pinfunction "~{TS}_6") (pintype "bidirectional"))
    )
    (net (code "72") (name "unconnected-(J17-NC-PadRSV2)") (class "Default")
      (node (ref "J17") (pin "RSV2") (pinfunction "NC_RSV2") (pintype "bidirectional"))
    )
    (net (code "73") (name "unconnected-(J17-RSV-PadRSV1)") (class "Default")
      (node (ref "J17") (pin "RSV1") (pinfunction "RSV_RSV1") (pintype "bidirectional"))
    )
    (net (code "74") (name "unconnected-(J18-Pad3)") (class "Default")
      (node (ref "J18") (pin "3") (pinfunction "3_3") (pintype "passive"))
    )
    (net (code "75") (name "unconnected-(RTC1-32KHZ-Pad1)") (class "Default")
      (node (ref "RTC1") (pin "1") (pinfunction "32KHZ_1") (pintype "output"))
    )
    (net (code "76") (name "unconnected-(U1-CLK-Pad38)") (class "Default")
      (node (ref "U1") (pin "38") (pinfunction "CLK_38") (pintype "input"))
    )
    (net (code "77") (name "unconnected-(U1-IO0-Pad33)") (class "Default")
      (node (ref "U1") (pin "33") (pinfunction "IO0_33") (pintype "bidirectional"))
    )
    (net (code "78") (name "unconnected-(U1-IO2-Pad34)") (class "Default")
      (node (ref "U1") (pin "34") (pinfunction "IO2_34") (pintype "bidirectional"))
    )
    (net (code "79") (name "unconnected-(U1-RXD0-Pad24)") (class "Default")
      (node (ref "U1") (pin "24") (pinfunction "RXD0_24") (pintype "input"))
    )
    (net (code "80") (name "unconnected-(U1-SD0-Pad37)") (class "Default")
      (node (ref "U1") (pin "37") (pinfunction "SD0_37") (pintype "bidirectional"))
    )
    (net (code "81") (name "unconnected-(U1-SD1-Pad36)") (class "Default")
      (node (ref "U1") (pin "36") (pinfunction "SD1_36") (pintype "bidirectional"))
    )
    (net (code "82") (name "unconnected-(U1-TXD0-Pad23)") (class "Default")
      (node (ref "U1") (pin "23") (pinfunction "TXD0_23") (pintype "output"))
    )
    (net (code "83") (name "unconnected-(VR1-PadMH1)") (class "Default")
      (node (ref "VR1") (pin "MH1") (pinfunction "MH1_MH1") (pintype "bidirectional"))
    )
    (net (code "84") (name "unconnected-(VR1-PadMH2)") (class "Default")
      (node (ref "VR1") (pin "MH2") (pinfunction "MH2_MH2") (pintype "bidirectional"))
    )
    (net (code "85") (name "~{INT}") (class "Default")
      (node (ref "IC2") (pin "13") (pinfunction "~{INT}_13") (pintype "bidirectional"))
      (node (ref "IC4") (pin "17") (pinfunction "~{INT}_17") (pintype "bidirectional"))
      (node (ref "U1") (pin "32") (pinfunction "IO4_32") (pintype "bidirectional"))
    )
    (net (code "86") (name "~{RST}") (class "Default")
      (node (ref "J5") (pin "5") (pinfunction "5_5") (pintype "passive"))
      (node (ref "J9") (pin "18") (pinfunction "18_18") (pintype "passive"))
      (node (ref "RTC1") (pin "4") (pinfunction "RST_4") (pintype "bidirectional"))
      (node (ref "U1") (pin "2") (pinfunction "EN_2") (pintype "input"))
    )
  )
)
